# sensor-board.net
KiCad netlist of a schematic drawn in EAGLE
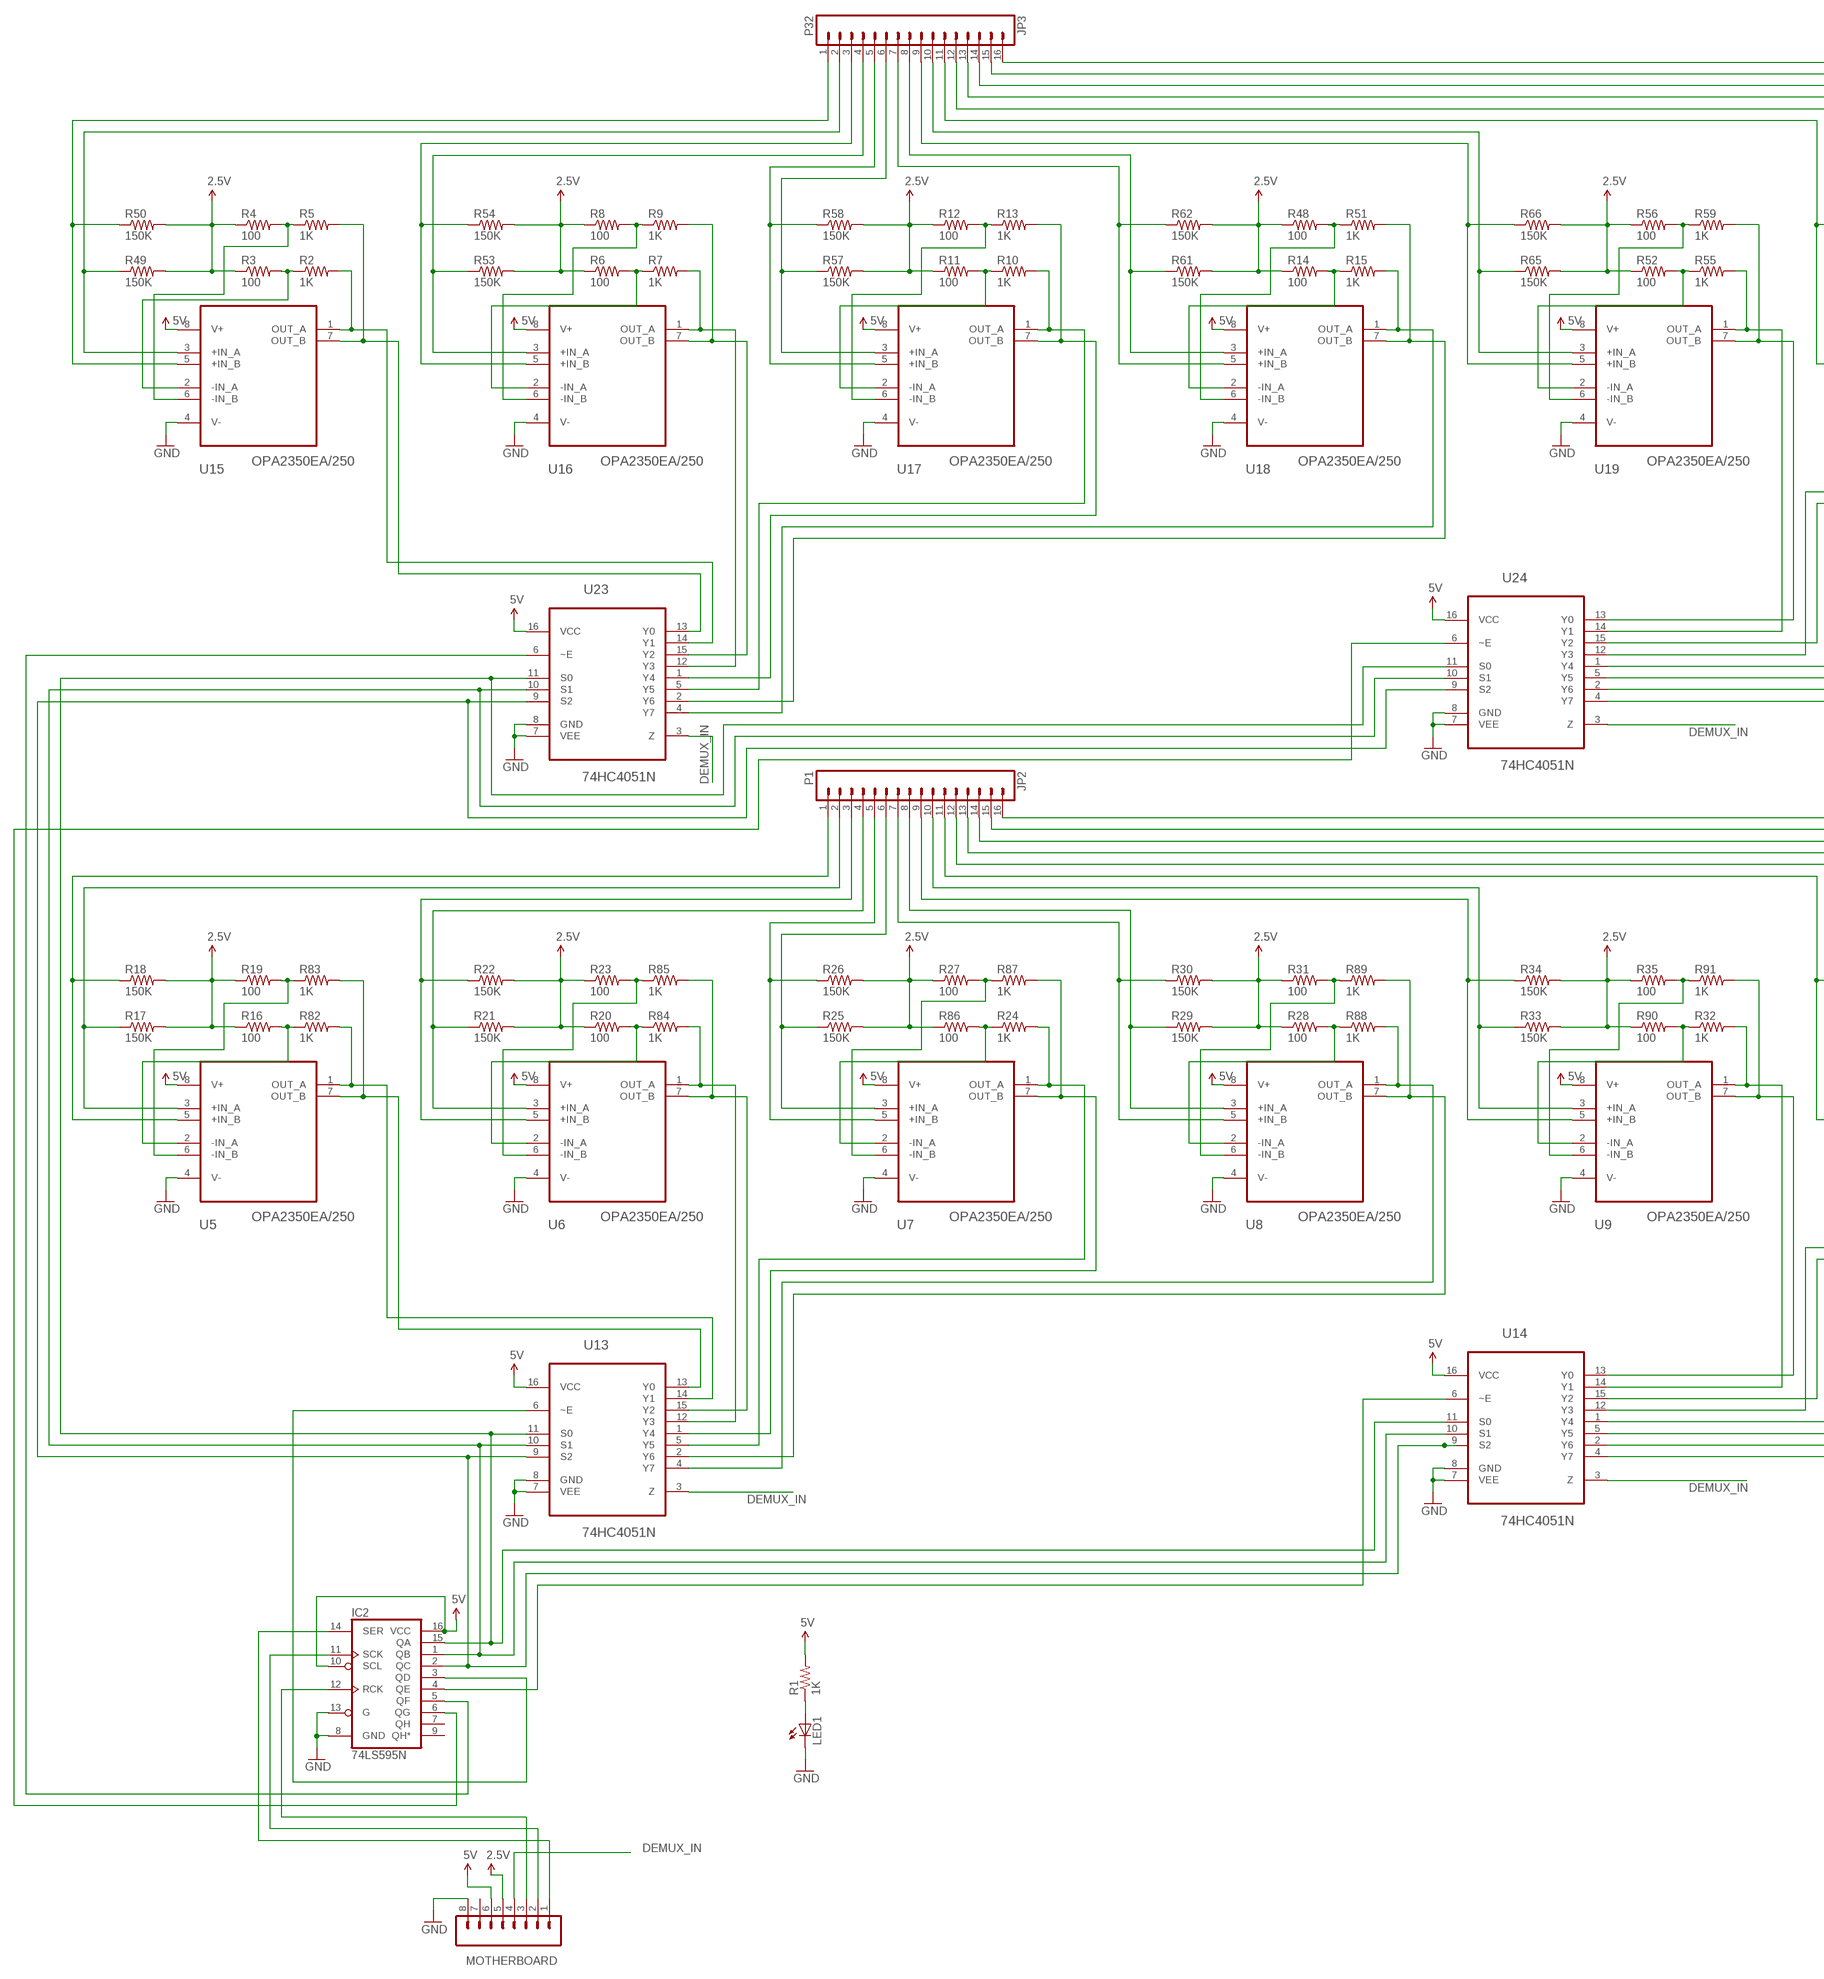
[diagram p0: schematic, sheet 1, part 1 of 2]
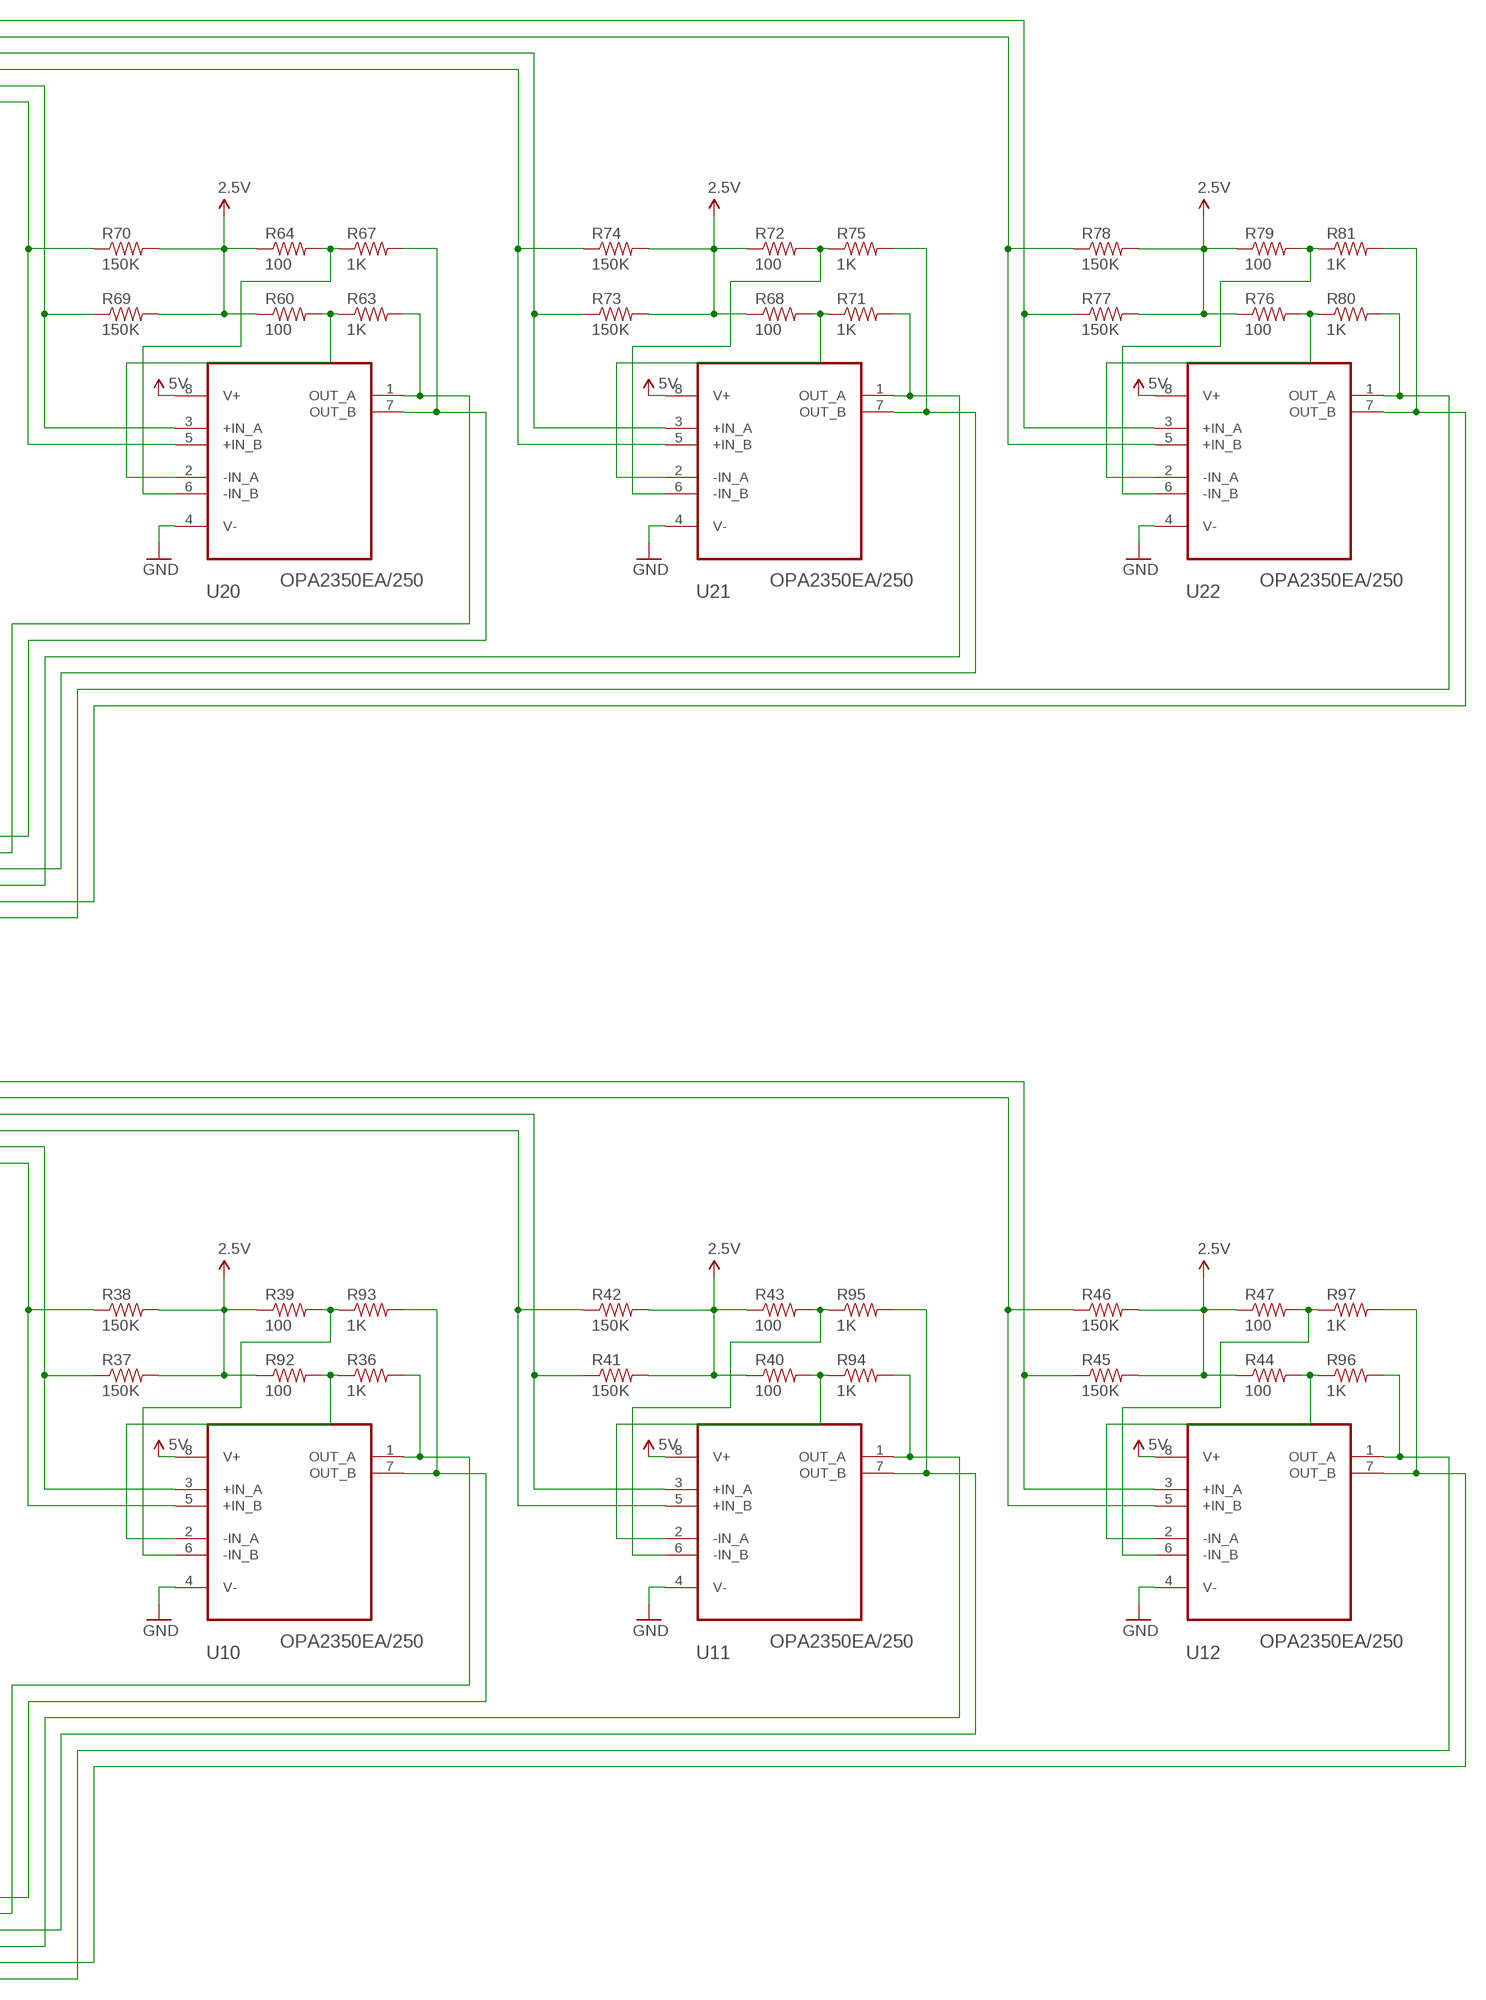
[diagram p1: schematic, sheet 1, part 2 of 2]

(export (version "E")
  (design (tool "Eeschema 10.0.6"))
  (components
    (comp (ref "IC2")
      (value "74LS595N")
      (footprint "eagle-import:DIL16")
      (libsource (lib "eagle-import") (part "74595NLS"))
    )
    (comp (ref "JP2")
      (value "P1")
      (footprint "eagle-import:1X16_LOCK")
      (libsource (lib "eagle-import") (part "M16LOCK"))
    )
    (comp (ref "JP3")
      (value "P32")
      (footprint "eagle-import:1X16_LOCK")
      (libsource (lib "eagle-import") (part "M16LOCK"))
    )
    (comp (ref "LED1")
      (value "LED0603")
      (footprint "eagle-import:LED-0603")
      (libsource (lib "eagle-import") (part "LED0603"))
    )
    (comp (ref "MOTHERBOARD")
      (value "M08LONGPADS")
      (footprint "eagle-import:1X08_LONGPADS")
      (libsource (lib "eagle-import") (part "M08LONGPADS"))
    )
    (comp (ref "R1")
      (value "1K")
      (footprint "eagle-import:0805")
      (libsource (lib "eagle-import") (part "RESISTOR0805-RES"))
    )
    (comp (ref "R2")
      (value "1K")
      (footprint "eagle-import:0805")
      (libsource (lib "eagle-import") (part "RESISTOR0805-RES"))
    )
    (comp (ref "R3")
      (value "100")
      (footprint "eagle-import:0805")
      (libsource (lib "eagle-import") (part "RESISTOR0805-RES"))
    )
    (comp (ref "R4")
      (value "100")
      (footprint "eagle-import:0805")
      (libsource (lib "eagle-import") (part "RESISTOR0805-RES"))
    )
    (comp (ref "R5")
      (value "1K")
      (footprint "eagle-import:0805")
      (libsource (lib "eagle-import") (part "RESISTOR0805-RES"))
    )
    (comp (ref "R6")
      (value "100")
      (footprint "eagle-import:0805")
      (libsource (lib "eagle-import") (part "RESISTOR0805-RES"))
    )
    (comp (ref "R7")
      (value "1K")
      (footprint "eagle-import:0805")
      (libsource (lib "eagle-import") (part "RESISTOR0805-RES"))
    )
    (comp (ref "R8")
      (value "100")
      (footprint "eagle-import:0805")
      (libsource (lib "eagle-import") (part "RESISTOR0805-RES"))
    )
    (comp (ref "R9")
      (value "1K")
      (footprint "eagle-import:0805")
      (libsource (lib "eagle-import") (part "RESISTOR0805-RES"))
    )
    (comp (ref "R10")
      (value "1K")
      (footprint "eagle-import:0805")
      (libsource (lib "eagle-import") (part "RESISTOR0805-RES"))
    )
    (comp (ref "R11")
      (value "100")
      (footprint "eagle-import:0805")
      (libsource (lib "eagle-import") (part "RESISTOR0805-RES"))
    )
    (comp (ref "R12")
      (value "100")
      (footprint "eagle-import:0805")
      (libsource (lib "eagle-import") (part "RESISTOR0805-RES"))
    )
    (comp (ref "R13")
      (value "1K")
      (footprint "eagle-import:0805")
      (libsource (lib "eagle-import") (part "RESISTOR0805-RES"))
    )
    (comp (ref "R14")
      (value "100")
      (footprint "eagle-import:0805")
      (libsource (lib "eagle-import") (part "RESISTOR0805-RES"))
    )
    (comp (ref "R15")
      (value "1K")
      (footprint "eagle-import:0805")
      (libsource (lib "eagle-import") (part "RESISTOR0805-RES"))
    )
    (comp (ref "R16")
      (value "100")
      (footprint "eagle-import:0805")
      (libsource (lib "eagle-import") (part "RESISTOR0805-RES"))
    )
    (comp (ref "R17")
      (value "150K")
      (footprint "eagle-import:0805")
      (libsource (lib "eagle-import") (part "RESISTOR0805-RES"))
    )
    (comp (ref "R18")
      (value "150K")
      (footprint "eagle-import:0805")
      (libsource (lib "eagle-import") (part "RESISTOR0805-RES"))
    )
    (comp (ref "R19")
      (value "100")
      (footprint "eagle-import:0805")
      (libsource (lib "eagle-import") (part "RESISTOR0805-RES"))
    )
    (comp (ref "R20")
      (value "100")
      (footprint "eagle-import:0805")
      (libsource (lib "eagle-import") (part "RESISTOR0805-RES"))
    )
    (comp (ref "R21")
      (value "150K")
      (footprint "eagle-import:0805")
      (libsource (lib "eagle-import") (part "RESISTOR0805-RES"))
    )
    (comp (ref "R22")
      (value "150K")
      (footprint "eagle-import:0805")
      (libsource (lib "eagle-import") (part "RESISTOR0805-RES"))
    )
    (comp (ref "R23")
      (value "100")
      (footprint "eagle-import:0805")
      (libsource (lib "eagle-import") (part "RESISTOR0805-RES"))
    )
    (comp (ref "R24")
      (value "1K")
      (footprint "eagle-import:0805")
      (libsource (lib "eagle-import") (part "RESISTOR0805-RES"))
    )
    (comp (ref "R25")
      (value "150K")
      (footprint "eagle-import:0805")
      (libsource (lib "eagle-import") (part "RESISTOR0805-RES"))
    )
    (comp (ref "R26")
      (value "150K")
      (footprint "eagle-import:0805")
      (libsource (lib "eagle-import") (part "RESISTOR0805-RES"))
    )
    (comp (ref "R27")
      (value "100")
      (footprint "eagle-import:0805")
      (libsource (lib "eagle-import") (part "RESISTOR0805-RES"))
    )
    (comp (ref "R28")
      (value "100")
      (footprint "eagle-import:0805")
      (libsource (lib "eagle-import") (part "RESISTOR0805-RES"))
    )
    (comp (ref "R29")
      (value "150K")
      (footprint "eagle-import:0805")
      (libsource (lib "eagle-import") (part "RESISTOR0805-RES"))
    )
    (comp (ref "R30")
      (value "150K")
      (footprint "eagle-import:0805")
      (libsource (lib "eagle-import") (part "RESISTOR0805-RES"))
    )
    (comp (ref "R31")
      (value "100")
      (footprint "eagle-import:0805")
      (libsource (lib "eagle-import") (part "RESISTOR0805-RES"))
    )
    (comp (ref "R32")
      (value "1K")
      (footprint "eagle-import:0805")
      (libsource (lib "eagle-import") (part "RESISTOR0805-RES"))
    )
    (comp (ref "R33")
      (value "150K")
      (footprint "eagle-import:0805")
      (libsource (lib "eagle-import") (part "RESISTOR0805-RES"))
    )
    (comp (ref "R34")
      (value "150K")
      (footprint "eagle-import:0805")
      (libsource (lib "eagle-import") (part "RESISTOR0805-RES"))
    )
    (comp (ref "R35")
      (value "100")
      (footprint "eagle-import:0805")
      (libsource (lib "eagle-import") (part "RESISTOR0805-RES"))
    )
    (comp (ref "R36")
      (value "1K")
      (footprint "eagle-import:0805")
      (libsource (lib "eagle-import") (part "RESISTOR0805-RES"))
    )
    (comp (ref "R37")
      (value "150K")
      (footprint "eagle-import:0805")
      (libsource (lib "eagle-import") (part "RESISTOR0805-RES"))
    )
    (comp (ref "R38")
      (value "150K")
      (footprint "eagle-import:0805")
      (libsource (lib "eagle-import") (part "RESISTOR0805-RES"))
    )
    (comp (ref "R39")
      (value "100")
      (footprint "eagle-import:0805")
      (libsource (lib "eagle-import") (part "RESISTOR0805-RES"))
    )
    (comp (ref "R40")
      (value "100")
      (footprint "eagle-import:0805")
      (libsource (lib "eagle-import") (part "RESISTOR0805-RES"))
    )
    (comp (ref "R41")
      (value "150K")
      (footprint "eagle-import:0805")
      (libsource (lib "eagle-import") (part "RESISTOR0805-RES"))
    )
    (comp (ref "R42")
      (value "150K")
      (footprint "eagle-import:0805")
      (libsource (lib "eagle-import") (part "RESISTOR0805-RES"))
    )
    (comp (ref "R43")
      (value "100")
      (footprint "eagle-import:0805")
      (libsource (lib "eagle-import") (part "RESISTOR0805-RES"))
    )
    (comp (ref "R44")
      (value "100")
      (footprint "eagle-import:0805")
      (libsource (lib "eagle-import") (part "RESISTOR0805-RES"))
    )
    (comp (ref "R45")
      (value "150K")
      (footprint "eagle-import:0805")
      (libsource (lib "eagle-import") (part "RESISTOR0805-RES"))
    )
    (comp (ref "R46")
      (value "150K")
      (footprint "eagle-import:0805")
      (libsource (lib "eagle-import") (part "RESISTOR0805-RES"))
    )
    (comp (ref "R47")
      (value "100")
      (footprint "eagle-import:0805")
      (libsource (lib "eagle-import") (part "RESISTOR0805-RES"))
    )
    (comp (ref "R48")
      (value "100")
      (footprint "eagle-import:0805")
      (libsource (lib "eagle-import") (part "RESISTOR0805-RES"))
    )
    (comp (ref "R49")
      (value "150K")
      (footprint "eagle-import:0805")
      (libsource (lib "eagle-import") (part "RESISTOR0805-RES"))
    )
    (comp (ref "R50")
      (value "150K")
      (footprint "eagle-import:0805")
      (libsource (lib "eagle-import") (part "RESISTOR0805-RES"))
    )
    (comp (ref "R51")
      (value "1K")
      (footprint "eagle-import:0805")
      (libsource (lib "eagle-import") (part "RESISTOR0805-RES"))
    )
    (comp (ref "R52")
      (value "100")
      (footprint "eagle-import:0805")
      (libsource (lib "eagle-import") (part "RESISTOR0805-RES"))
    )
    (comp (ref "R53")
      (value "150K")
      (footprint "eagle-import:0805")
      (libsource (lib "eagle-import") (part "RESISTOR0805-RES"))
    )
    (comp (ref "R54")
      (value "150K")
      (footprint "eagle-import:0805")
      (libsource (lib "eagle-import") (part "RESISTOR0805-RES"))
    )
    (comp (ref "R55")
      (value "1K")
      (footprint "eagle-import:0805")
      (libsource (lib "eagle-import") (part "RESISTOR0805-RES"))
    )
    (comp (ref "R56")
      (value "100")
      (footprint "eagle-import:0805")
      (libsource (lib "eagle-import") (part "RESISTOR0805-RES"))
    )
    (comp (ref "R57")
      (value "150K")
      (footprint "eagle-import:0805")
      (libsource (lib "eagle-import") (part "RESISTOR0805-RES"))
    )
    (comp (ref "R58")
      (value "150K")
      (footprint "eagle-import:0805")
      (libsource (lib "eagle-import") (part "RESISTOR0805-RES"))
    )
    (comp (ref "R59")
      (value "1K")
      (footprint "eagle-import:0805")
      (libsource (lib "eagle-import") (part "RESISTOR0805-RES"))
    )
    (comp (ref "R60")
      (value "100")
      (footprint "eagle-import:0805")
      (libsource (lib "eagle-import") (part "RESISTOR0805-RES"))
    )
    (comp (ref "R61")
      (value "150K")
      (footprint "eagle-import:0805")
      (libsource (lib "eagle-import") (part "RESISTOR0805-RES"))
    )
    (comp (ref "R62")
      (value "150K")
      (footprint "eagle-import:0805")
      (libsource (lib "eagle-import") (part "RESISTOR0805-RES"))
    )
    (comp (ref "R63")
      (value "1K")
      (footprint "eagle-import:0805")
      (libsource (lib "eagle-import") (part "RESISTOR0805-RES"))
    )
    (comp (ref "R64")
      (value "100")
      (footprint "eagle-import:0805")
      (libsource (lib "eagle-import") (part "RESISTOR0805-RES"))
    )
    (comp (ref "R65")
      (value "150K")
      (footprint "eagle-import:0805")
      (libsource (lib "eagle-import") (part "RESISTOR0805-RES"))
    )
    (comp (ref "R66")
      (value "150K")
      (footprint "eagle-import:0805")
      (libsource (lib "eagle-import") (part "RESISTOR0805-RES"))
    )
    (comp (ref "R67")
      (value "1K")
      (footprint "eagle-import:0805")
      (libsource (lib "eagle-import") (part "RESISTOR0805-RES"))
    )
    (comp (ref "R68")
      (value "100")
      (footprint "eagle-import:0805")
      (libsource (lib "eagle-import") (part "RESISTOR0805-RES"))
    )
    (comp (ref "R69")
      (value "150K")
      (footprint "eagle-import:0805")
      (libsource (lib "eagle-import") (part "RESISTOR0805-RES"))
    )
    (comp (ref "R70")
      (value "150K")
      (footprint "eagle-import:0805")
      (libsource (lib "eagle-import") (part "RESISTOR0805-RES"))
    )
    (comp (ref "R71")
      (value "1K")
      (footprint "eagle-import:0805")
      (libsource (lib "eagle-import") (part "RESISTOR0805-RES"))
    )
    (comp (ref "R72")
      (value "100")
      (footprint "eagle-import:0805")
      (libsource (lib "eagle-import") (part "RESISTOR0805-RES"))
    )
    (comp (ref "R73")
      (value "150K")
      (footprint "eagle-import:0805")
      (libsource (lib "eagle-import") (part "RESISTOR0805-RES"))
    )
    (comp (ref "R74")
      (value "150K")
      (footprint "eagle-import:0805")
      (libsource (lib "eagle-import") (part "RESISTOR0805-RES"))
    )
    (comp (ref "R75")
      (value "1K")
      (footprint "eagle-import:0805")
      (libsource (lib "eagle-import") (part "RESISTOR0805-RES"))
    )
    (comp (ref "R76")
      (value "100")
      (footprint "eagle-import:0805")
      (libsource (lib "eagle-import") (part "RESISTOR0805-RES"))
    )
    (comp (ref "R77")
      (value "150K")
      (footprint "eagle-import:0805")
      (libsource (lib "eagle-import") (part "RESISTOR0805-RES"))
    )
    (comp (ref "R78")
      (value "150K")
      (footprint "eagle-import:0805")
      (libsource (lib "eagle-import") (part "RESISTOR0805-RES"))
    )
    (comp (ref "R79")
      (value "100")
      (footprint "eagle-import:0805")
      (libsource (lib "eagle-import") (part "RESISTOR0805-RES"))
    )
    (comp (ref "R80")
      (value "1K")
      (footprint "eagle-import:0805")
      (libsource (lib "eagle-import") (part "RESISTOR0805-RES"))
    )
    (comp (ref "R81")
      (value "1K")
      (footprint "eagle-import:0805")
      (libsource (lib "eagle-import") (part "RESISTOR0805-RES"))
    )
    (comp (ref "R82")
      (value "1K")
      (footprint "eagle-import:0805")
      (libsource (lib "eagle-import") (part "RESISTOR0805-RES"))
    )
    (comp (ref "R83")
      (value "1K")
      (footprint "eagle-import:0805")
      (libsource (lib "eagle-import") (part "RESISTOR0805-RES"))
    )
    (comp (ref "R84")
      (value "1K")
      (footprint "eagle-import:0805")
      (libsource (lib "eagle-import") (part "RESISTOR0805-RES"))
    )
    (comp (ref "R85")
      (value "1K")
      (footprint "eagle-import:0805")
      (libsource (lib "eagle-import") (part "RESISTOR0805-RES"))
    )
    (comp (ref "R86")
      (value "100")
      (footprint "eagle-import:0805")
      (libsource (lib "eagle-import") (part "RESISTOR0805-RES"))
    )
    (comp (ref "R87")
      (value "1K")
      (footprint "eagle-import:0805")
      (libsource (lib "eagle-import") (part "RESISTOR0805-RES"))
    )
    (comp (ref "R88")
      (value "1K")
      (footprint "eagle-import:0805")
      (libsource (lib "eagle-import") (part "RESISTOR0805-RES"))
    )
    (comp (ref "R89")
      (value "1K")
      (footprint "eagle-import:0805")
      (libsource (lib "eagle-import") (part "RESISTOR0805-RES"))
    )
    (comp (ref "R90")
      (value "100")
      (footprint "eagle-import:0805")
      (libsource (lib "eagle-import") (part "RESISTOR0805-RES"))
    )
    (comp (ref "R91")
      (value "1K")
      (footprint "eagle-import:0805")
      (libsource (lib "eagle-import") (part "RESISTOR0805-RES"))
    )
    (comp (ref "R92")
      (value "100")
      (footprint "eagle-import:0805")
      (libsource (lib "eagle-import") (part "RESISTOR0805-RES"))
    )
    (comp (ref "R93")
      (value "1K")
      (footprint "eagle-import:0805")
      (libsource (lib "eagle-import") (part "RESISTOR0805-RES"))
    )
    (comp (ref "R94")
      (value "1K")
      (footprint "eagle-import:0805")
      (libsource (lib "eagle-import") (part "RESISTOR0805-RES"))
    )
    (comp (ref "R95")
      (value "1K")
      (footprint "eagle-import:0805")
      (libsource (lib "eagle-import") (part "RESISTOR0805-RES"))
    )
    (comp (ref "R96")
      (value "1K")
      (footprint "eagle-import:0805")
      (libsource (lib "eagle-import") (part "RESISTOR0805-RES"))
    )
    (comp (ref "R97")
      (value "1K")
      (footprint "eagle-import:0805")
      (libsource (lib "eagle-import") (part "RESISTOR0805-RES"))
    )
    (comp (ref "U5")
      (value "OPA2350EA/250")
      (footprint "eagle-import:SOP65P490X110-8N")
      (libsource (lib "eagle-import") (part "OPA2350EA/250"))
    )
    (comp (ref "U6")
      (value "OPA2350EA/250")
      (footprint "eagle-import:SOP65P490X110-8N")
      (libsource (lib "eagle-import") (part "OPA2350EA/250"))
    )
    (comp (ref "U7")
      (value "OPA2350EA/250")
      (footprint "eagle-import:SOP65P490X110-8N")
      (libsource (lib "eagle-import") (part "OPA2350EA/250"))
    )
    (comp (ref "U8")
      (value "OPA2350EA/250")
      (footprint "eagle-import:SOP65P490X110-8N")
      (libsource (lib "eagle-import") (part "OPA2350EA/250"))
    )
    (comp (ref "U9")
      (value "OPA2350EA/250")
      (footprint "eagle-import:SOP65P490X110-8N")
      (libsource (lib "eagle-import") (part "OPA2350EA/250"))
    )
    (comp (ref "U10")
      (value "OPA2350EA/250")
      (footprint "eagle-import:SOP65P490X110-8N")
      (libsource (lib "eagle-import") (part "OPA2350EA/250"))
    )
    (comp (ref "U11")
      (value "OPA2350EA/250")
      (footprint "eagle-import:SOP65P490X110-8N")
      (libsource (lib "eagle-import") (part "OPA2350EA/250"))
    )
    (comp (ref "U12")
      (value "OPA2350EA/250")
      (footprint "eagle-import:SOP65P490X110-8N")
      (libsource (lib "eagle-import") (part "OPA2350EA/250"))
    )
    (comp (ref "U13")
      (value "74HC4051N")
      (footprint "eagle-import:DIP254P762X420-16")
      (libsource (lib "eagle-import") (part "74HC4051N"))
    )
    (comp (ref "U14")
      (value "74HC4051N")
      (footprint "eagle-import:DIP254P762X420-16")
      (libsource (lib "eagle-import") (part "74HC4051N"))
    )
    (comp (ref "U15")
      (value "OPA2350EA/250")
      (footprint "eagle-import:SOP65P490X110-8N")
      (libsource (lib "eagle-import") (part "OPA2350EA/250"))
    )
    (comp (ref "U16")
      (value "OPA2350EA/250")
      (footprint "eagle-import:SOP65P490X110-8N")
      (libsource (lib "eagle-import") (part "OPA2350EA/250"))
    )
    (comp (ref "U17")
      (value "OPA2350EA/250")
      (footprint "eagle-import:SOP65P490X110-8N")
      (libsource (lib "eagle-import") (part "OPA2350EA/250"))
    )
    (comp (ref "U18")
      (value "OPA2350EA/250")
      (footprint "eagle-import:SOP65P490X110-8N")
      (libsource (lib "eagle-import") (part "OPA2350EA/250"))
    )
    (comp (ref "U19")
      (value "OPA2350EA/250")
      (footprint "eagle-import:SOP65P490X110-8N")
      (libsource (lib "eagle-import") (part "OPA2350EA/250"))
    )
    (comp (ref "U20")
      (value "OPA2350EA/250")
      (footprint "eagle-import:SOP65P490X110-8N")
      (libsource (lib "eagle-import") (part "OPA2350EA/250"))
    )
    (comp (ref "U21")
      (value "OPA2350EA/250")
      (footprint "eagle-import:SOP65P490X110-8N")
      (libsource (lib "eagle-import") (part "OPA2350EA/250"))
    )
    (comp (ref "U22")
      (value "OPA2350EA/250")
      (footprint "eagle-import:SOP65P490X110-8N")
      (libsource (lib "eagle-import") (part "OPA2350EA/250"))
    )
    (comp (ref "U23")
      (value "74HC4051N")
      (footprint "eagle-import:DIP254P762X420-16")
      (libsource (lib "eagle-import") (part "74HC4051N"))
    )
    (comp (ref "U24")
      (value "74HC4051N")
      (footprint "eagle-import:DIP254P762X420-16")
      (libsource (lib "eagle-import") (part "74HC4051N"))
    )
  )
  (nets
    (net (code "1") (name "/DEMUX_IN") (class "Default")
      (node (ref "MOTHERBOARD") (pin "4") (pinfunction "4_4") (pintype "passive"))
      (node (ref "U13") (pin "3") (pinfunction "Z_3") (pintype "bidirectional"))
      (node (ref "U14") (pin "3") (pinfunction "Z_3") (pintype "bidirectional"))
      (node (ref "U23") (pin "3") (pinfunction "Z_3") (pintype "bidirectional"))
      (node (ref "U24") (pin "3") (pinfunction "Z_3") (pintype "bidirectional"))
    )
    (net (code "2") (name "2.5V") (class "Default")
      (node (ref "MOTHERBOARD") (pin "5") (pinfunction "5_5") (pintype "passive"))
      (node (ref "R11") (pin "1") (pinfunction "1_1") (pintype "passive"))
      (node (ref "R12") (pin "1") (pinfunction "1_1") (pintype "passive"))
      (node (ref "R14") (pin "1") (pinfunction "1_1") (pintype "passive"))
      (node (ref "R16") (pin "1") (pinfunction "1_1") (pintype "passive"))
      (node (ref "R17") (pin "2") (pinfunction "2_2") (pintype "passive"))
      (node (ref "R18") (pin "2") (pinfunction "2_2") (pintype "passive"))
      (node (ref "R19") (pin "1") (pinfunction "1_1") (pintype "passive"))
      (node (ref "R20") (pin "1") (pinfunction "1_1") (pintype "passive"))
      (node (ref "R21") (pin "2") (pinfunction "2_2") (pintype "passive"))
      (node (ref "R22") (pin "2") (pinfunction "2_2") (pintype "passive"))
      (node (ref "R23") (pin "1") (pinfunction "1_1") (pintype "passive"))
      (node (ref "R25") (pin "2") (pinfunction "2_2") (pintype "passive"))
      (node (ref "R26") (pin "2") (pinfunction "2_2") (pintype "passive"))
      (node (ref "R27") (pin "1") (pinfunction "1_1") (pintype "passive"))
      (node (ref "R28") (pin "1") (pinfunction "1_1") (pintype "passive"))
      (node (ref "R29") (pin "2") (pinfunction "2_2") (pintype "passive"))
      (node (ref "R3") (pin "1") (pinfunction "1_1") (pintype "passive"))
      (node (ref "R30") (pin "2") (pinfunction "2_2") (pintype "passive"))
      (node (ref "R31") (pin "1") (pinfunction "1_1") (pintype "passive"))
      (node (ref "R33") (pin "2") (pinfunction "2_2") (pintype "passive"))
      (node (ref "R34") (pin "2") (pinfunction "2_2") (pintype "passive"))
      (node (ref "R35") (pin "1") (pinfunction "1_1") (pintype "passive"))
      (node (ref "R37") (pin "2") (pinfunction "2_2") (pintype "passive"))
      (node (ref "R38") (pin "2") (pinfunction "2_2") (pintype "passive"))
      (node (ref "R39") (pin "1") (pinfunction "1_1") (pintype "passive"))
      (node (ref "R4") (pin "1") (pinfunction "1_1") (pintype "passive"))
      (node (ref "R40") (pin "1") (pinfunction "1_1") (pintype "passive"))
      (node (ref "R41") (pin "2") (pinfunction "2_2") (pintype "passive"))
      (node (ref "R42") (pin "2") (pinfunction "2_2") (pintype "passive"))
      (node (ref "R43") (pin "1") (pinfunction "1_1") (pintype "passive"))
      (node (ref "R44") (pin "1") (pinfunction "1_1") (pintype "passive"))
      (node (ref "R45") (pin "2") (pinfunction "2_2") (pintype "passive"))
      (node (ref "R46") (pin "2") (pinfunction "2_2") (pintype "passive"))
      (node (ref "R47") (pin "1") (pinfunction "1_1") (pintype "passive"))
      (node (ref "R48") (pin "1") (pinfunction "1_1") (pintype "passive"))
      (node (ref "R49") (pin "2") (pinfunction "2_2") (pintype "passive"))
      (node (ref "R50") (pin "2") (pinfunction "2_2") (pintype "passive"))
      (node (ref "R52") (pin "1") (pinfunction "1_1") (pintype "passive"))
      (node (ref "R53") (pin "2") (pinfunction "2_2") (pintype "passive"))
      (node (ref "R54") (pin "2") (pinfunction "2_2") (pintype "passive"))
      (node (ref "R56") (pin "1") (pinfunction "1_1") (pintype "passive"))
      (node (ref "R57") (pin "2") (pinfunction "2_2") (pintype "passive"))
      (node (ref "R58") (pin "2") (pinfunction "2_2") (pintype "passive"))
      (node (ref "R6") (pin "1") (pinfunction "1_1") (pintype "passive"))
      (node (ref "R60") (pin "1") (pinfunction "1_1") (pintype "passive"))
      (node (ref "R61") (pin "2") (pinfunction "2_2") (pintype "passive"))
      (node (ref "R62") (pin "2") (pinfunction "2_2") (pintype "passive"))
      (node (ref "R64") (pin "1") (pinfunction "1_1") (pintype "passive"))
      (node (ref "R65") (pin "2") (pinfunction "2_2") (pintype "passive"))
      (node (ref "R66") (pin "2") (pinfunction "2_2") (pintype "passive"))
      (node (ref "R68") (pin "1") (pinfunction "1_1") (pintype "passive"))
      (node (ref "R69") (pin "2") (pinfunction "2_2") (pintype "passive"))
      (node (ref "R70") (pin "2") (pinfunction "2_2") (pintype "passive"))
      (node (ref "R72") (pin "1") (pinfunction "1_1") (pintype "passive"))
      (node (ref "R73") (pin "2") (pinfunction "2_2") (pintype "passive"))
      (node (ref "R74") (pin "2") (pinfunction "2_2") (pintype "passive"))
      (node (ref "R76") (pin "1") (pinfunction "1_1") (pintype "passive"))
      (node (ref "R77") (pin "2") (pinfunction "2_2") (pintype "passive"))
      (node (ref "R78") (pin "2") (pinfunction "2_2") (pintype "passive"))
      (node (ref "R79") (pin "1") (pinfunction "1_1") (pintype "passive"))
      (node (ref "R8") (pin "1") (pinfunction "1_1") (pintype "passive"))
      (node (ref "R86") (pin "1") (pinfunction "1_1") (pintype "passive"))
      (node (ref "R90") (pin "1") (pinfunction "1_1") (pintype "passive"))
      (node (ref "R92") (pin "1") (pinfunction "1_1") (pintype "passive"))
    )
    (net (code "3") (name "5V") (class "Default")
      (node (ref "IC2") (pin "10") (pinfunction "SCL_10") (pintype "input"))
      (node (ref "IC2") (pin "16") (pinfunction "VCC_16") (pintype "power_in"))
      (node (ref "MOTHERBOARD") (pin "6") (pinfunction "6_6") (pintype "passive"))
      (node (ref "R1") (pin "2") (pinfunction "2_2") (pintype "passive"))
      (node (ref "U10") (pin "8") (pinfunction "V+_8") (pintype "power_in"))
      (node (ref "U11") (pin "8") (pinfunction "V+_8") (pintype "power_in"))
      (node (ref "U12") (pin "8") (pinfunction "V+_8") (pintype "power_in"))
      (node (ref "U13") (pin "16") (pinfunction "VCC_16") (pintype "power_in"))
      (node (ref "U14") (pin "16") (pinfunction "VCC_16") (pintype "power_in"))
      (node (ref "U15") (pin "8") (pinfunction "V+_8") (pintype "power_in"))
      (node (ref "U16") (pin "8") (pinfunction "V+_8") (pintype "power_in"))
      (node (ref "U17") (pin "8") (pinfunction "V+_8") (pintype "power_in"))
      (node (ref "U18") (pin "8") (pinfunction "V+_8") (pintype "power_in"))
      (node (ref "U19") (pin "8") (pinfunction "V+_8") (pintype "power_in"))
      (node (ref "U20") (pin "8") (pinfunction "V+_8") (pintype "power_in"))
      (node (ref "U21") (pin "8") (pinfunction "V+_8") (pintype "power_in"))
      (node (ref "U22") (pin "8") (pinfunction "V+_8") (pintype "power_in"))
      (node (ref "U23") (pin "16") (pinfunction "VCC_16") (pintype "power_in"))
      (node (ref "U24") (pin "16") (pinfunction "VCC_16") (pintype "power_in"))
      (node (ref "U5") (pin "8") (pinfunction "V+_8") (pintype "power_in"))
      (node (ref "U6") (pin "8") (pinfunction "V+_8") (pintype "power_in"))
      (node (ref "U7") (pin "8") (pinfunction "V+_8") (pintype "power_in"))
      (node (ref "U8") (pin "8") (pinfunction "V+_8") (pintype "power_in"))
      (node (ref "U9") (pin "8") (pinfunction "V+_8") (pintype "power_in"))
    )
    (net (code "4") (name "GND") (class "Default")
      (node (ref "IC2") (pin "13") (pinfunction "G_13") (pintype "input"))
      (node (ref "IC2") (pin "8") (pinfunction "GND_8") (pintype "power_in"))
      (node (ref "LED1") (pin "C") (pinfunction "C_C") (pintype "passive"))
      (node (ref "MOTHERBOARD") (pin "8") (pinfunction "8_8") (pintype "passive"))
      (node (ref "U10") (pin "4") (pinfunction "V-_4") (pintype "power_in"))
      (node (ref "U11") (pin "4") (pinfunction "V-_4") (pintype "power_in"))
      (node (ref "U12") (pin "4") (pinfunction "V-_4") (pintype "power_in"))
      (node (ref "U13") (pin "7") (pinfunction "VEE_7") (pintype "power_in"))
      (node (ref "U13") (pin "8") (pinfunction "GND_8") (pintype "passive"))
      (node (ref "U14") (pin "7") (pinfunction "VEE_7") (pintype "power_in"))
      (node (ref "U14") (pin "8") (pinfunction "GND_8") (pintype "passive"))
      (node (ref "U15") (pin "4") (pinfunction "V-_4") (pintype "power_in"))
      (node (ref "U16") (pin "4") (pinfunction "V-_4") (pintype "power_in"))
      (node (ref "U17") (pin "4") (pinfunction "V-_4") (pintype "power_in"))
      (node (ref "U18") (pin "4") (pinfunction "V-_4") (pintype "power_in"))
      (node (ref "U19") (pin "4") (pinfunction "V-_4") (pintype "power_in"))
      (node (ref "U20") (pin "4") (pinfunction "V-_4") (pintype "power_in"))
      (node (ref "U21") (pin "4") (pinfunction "V-_4") (pintype "power_in"))
      (node (ref "U22") (pin "4") (pinfunction "V-_4") (pintype "power_in"))
      (node (ref "U23") (pin "7") (pinfunction "VEE_7") (pintype "power_in"))
      (node (ref "U23") (pin "8") (pinfunction "GND_8") (pintype "passive"))
      (node (ref "U24") (pin "7") (pinfunction "VEE_7") (pintype "power_in"))
      (node (ref "U24") (pin "8") (pinfunction "GND_8") (pintype "passive"))
      (node (ref "U5") (pin "4") (pinfunction "V-_4") (pintype "power_in"))
      (node (ref "U6") (pin "4") (pinfunction "V-_4") (pintype "power_in"))
      (node (ref "U7") (pin "4") (pinfunction "V-_4") (pintype "power_in"))
      (node (ref "U8") (pin "4") (pinfunction "V-_4") (pintype "power_in"))
      (node (ref "U9") (pin "4") (pinfunction "V-_4") (pintype "power_in"))
    )
    (net (code "5") (name "Net-(IC2-QA)") (class "Default")
      (node (ref "IC2") (pin "15") (pinfunction "QA_15") (pintype "tri_state"))
      (node (ref "U13") (pin "11") (pinfunction "S0_11") (pintype "input"))
      (node (ref "U14") (pin "11") (pinfunction "S0_11") (pintype "input"))
      (node (ref "U23") (pin "11") (pinfunction "S0_11") (pintype "input"))
      (node (ref "U24") (pin "11") (pinfunction "S0_11") (pintype "input"))
    )
    (net (code "6") (name "Net-(IC2-QB)") (class "Default")
      (node (ref "IC2") (pin "1") (pinfunction "QB_1") (pintype "tri_state"))
      (node (ref "U13") (pin "10") (pinfunction "S1_10") (pintype "input"))
      (node (ref "U14") (pin "10") (pinfunction "S1_10") (pintype "input"))
      (node (ref "U23") (pin "10") (pinfunction "S1_10") (pintype "input"))
      (node (ref "U24") (pin "10") (pinfunction "S1_10") (pintype "input"))
    )
    (net (code "7") (name "Net-(IC2-QC)") (class "Default")
      (node (ref "IC2") (pin "2") (pinfunction "QC_2") (pintype "tri_state"))
      (node (ref "U13") (pin "9") (pinfunction "S2_9") (pintype "input"))
      (node (ref "U14") (pin "9") (pinfunction "S2_9") (pintype "input"))
      (node (ref "U23") (pin "9") (pinfunction "S2_9") (pintype "input"))
      (node (ref "U24") (pin "9") (pinfunction "S2_9") (pintype "input"))
    )
    (net (code "8") (name "Net-(IC2-QD)") (class "Default")
      (node (ref "IC2") (pin "3") (pinfunction "QD_3") (pintype "tri_state"))
      (node (ref "U13") (pin "6") (pinfunction "~{E}_6") (pintype "input"))
    )
    (net (code "9") (name "Net-(IC2-QE)") (class "Default")
      (node (ref "IC2") (pin "4") (pinfunction "QE_4") (pintype "tri_state"))
      (node (ref "U14") (pin "6") (pinfunction "~{E}_6") (pintype "input"))
    )
    (net (code "10") (name "Net-(IC2-QF)") (class "Default")
      (node (ref "IC2") (pin "5") (pinfunction "QF_5") (pintype "tri_state"))
      (node (ref "U23") (pin "6") (pinfunction "~{E}_6") (pintype "input"))
    )
    (net (code "11") (name "Net-(IC2-QG)") (class "Default")
      (node (ref "IC2") (pin "6") (pinfunction "QG_6") (pintype "tri_state"))
      (node (ref "U24") (pin "6") (pinfunction "~{E}_6") (pintype "input"))
    )
    (net (code "12") (name "Net-(IC2-RCK)") (class "Default")
      (node (ref "IC2") (pin "12") (pinfunction "RCK_12") (pintype "input"))
      (node (ref "MOTHERBOARD") (pin "3") (pinfunction "3_3") (pintype "passive"))
    )
    (net (code "13") (name "Net-(IC2-SCK)") (class "Default")
      (node (ref "IC2") (pin "11") (pinfunction "SCK_11") (pintype "input"))
      (node (ref "MOTHERBOARD") (pin "2") (pinfunction "2_2") (pintype "passive"))
    )
    (net (code "14") (name "Net-(IC2-SER)") (class "Default")
      (node (ref "IC2") (pin "14") (pinfunction "SER_14") (pintype "input"))
      (node (ref "MOTHERBOARD") (pin "1") (pinfunction "1_1") (pintype "passive"))
    )
    (net (code "15") (name "Net-(LED1-PadA)") (class "Default")
      (node (ref "LED1") (pin "A") (pinfunction "A_A") (pintype "passive"))
      (node (ref "R1") (pin "1") (pinfunction "1_1") (pintype "passive"))
    )
    (net (code "16") (name "Net-(U5-+IN_A)") (class "Default")
      (node (ref "JP2") (pin "2") (pinfunction "2_2") (pintype "passive"))
      (node (ref "R17") (pin "1") (pinfunction "1_1") (pintype "passive"))
      (node (ref "U5") (pin "3") (pinfunction "+IN_A_3") (pintype "input"))
    )
    (net (code "17") (name "Net-(U5-+IN_B)") (class "Default")
      (node (ref "JP2") (pin "1") (pinfunction "1_1") (pintype "passive"))
      (node (ref "R18") (pin "1") (pinfunction "1_1") (pintype "passive"))
      (node (ref "U5") (pin "5") (pinfunction "+IN_B_5") (pintype "input"))
    )
    (net (code "18") (name "Net-(U5--IN_A)") (class "Default")
      (node (ref "R16") (pin "2") (pinfunction "2_2") (pintype "passive"))
      (node (ref "R82") (pin "1") (pinfunction "1_1") (pintype "passive"))
      (node (ref "U5") (pin "2") (pinfunction "-IN_A_2") (pintype "input"))
    )
    (net (code "19") (name "Net-(U5--IN_B)") (class "Default")
      (node (ref "R19") (pin "2") (pinfunction "2_2") (pintype "passive"))
      (node (ref "R83") (pin "1") (pinfunction "1_1") (pintype "passive"))
      (node (ref "U5") (pin "6") (pinfunction "-IN_B_6") (pintype "input"))
    )
    (net (code "20") (name "Net-(U6-+IN_A)") (class "Default")
      (node (ref "JP2") (pin "4") (pinfunction "4_4") (pintype "passive"))
      (node (ref "R21") (pin "1") (pinfunction "1_1") (pintype "passive"))
      (node (ref "U6") (pin "3") (pinfunction "+IN_A_3") (pintype "input"))
    )
    (net (code "21") (name "Net-(U6-+IN_B)") (class "Default")
      (node (ref "JP2") (pin "3") (pinfunction "3_3") (pintype "passive"))
      (node (ref "R22") (pin "1") (pinfunction "1_1") (pintype "passive"))
      (node (ref "U6") (pin "5") (pinfunction "+IN_B_5") (pintype "input"))
    )
    (net (code "22") (name "Net-(U6--IN_A)") (class "Default")
      (node (ref "R20") (pin "2") (pinfunction "2_2") (pintype "passive"))
      (node (ref "R84") (pin "1") (pinfunction "1_1") (pintype "passive"))
      (node (ref "U6") (pin "2") (pinfunction "-IN_A_2") (pintype "input"))
    )
    (net (code "23") (name "Net-(U6--IN_B)") (class "Default")
      (node (ref "R23") (pin "2") (pinfunction "2_2") (pintype "passive"))
      (node (ref "R85") (pin "1") (pinfunction "1_1") (pintype "passive"))
      (node (ref "U6") (pin "6") (pinfunction "-IN_B_6") (pintype "input"))
    )
    (net (code "24") (name "Net-(U7-+IN_A)") (class "Default")
      (node (ref "JP2") (pin "6") (pinfunction "6_6") (pintype "passive"))
      (node (ref "R25") (pin "1") (pinfunction "1_1") (pintype "passive"))
      (node (ref "U7") (pin "3") (pinfunction "+IN_A_3") (pintype "input"))
    )
    (net (code "25") (name "Net-(U7-+IN_B)") (class "Default")
      (node (ref "JP2") (pin "5") (pinfunction "5_5") (pintype "passive"))
      (node (ref "R26") (pin "1") (pinfunction "1_1") (pintype "passive"))
      (node (ref "U7") (pin "5") (pinfunction "+IN_B_5") (pintype "input"))
    )
    (net (code "26") (name "Net-(U7--IN_A)") (class "Default")
      (node (ref "R24") (pin "1") (pinfunction "1_1") (pintype "passive"))
      (node (ref "R86") (pin "2") (pinfunction "2_2") (pintype "passive"))
      (node (ref "U7") (pin "2") (pinfunction "-IN_A_2") (pintype "input"))
    )
    (net (code "27") (name "Net-(U7--IN_B)") (class "Default")
      (node (ref "R27") (pin "2") (pinfunction "2_2") (pintype "passive"))
      (node (ref "R87") (pin "1") (pinfunction "1_1") (pintype "passive"))
      (node (ref "U7") (pin "6") (pinfunction "-IN_B_6") (pintype "input"))
    )
    (net (code "28") (name "Net-(U8-+IN_A)") (class "Default")
      (node (ref "JP2") (pin "8") (pinfunction "8_8") (pintype "passive"))
      (node (ref "R29") (pin "1") (pinfunction "1_1") (pintype "passive"))
      (node (ref "U8") (pin "3") (pinfunction "+IN_A_3") (pintype "input"))
    )
    (net (code "29") (name "Net-(U8-+IN_B)") (class "Default")
      (node (ref "JP2") (pin "7") (pinfunction "7_7") (pintype "passive"))
      (node (ref "R30") (pin "1") (pinfunction "1_1") (pintype "passive"))
      (node (ref "U8") (pin "5") (pinfunction "+IN_B_5") (pintype "input"))
    )
    (net (code "30") (name "Net-(U8--IN_A)") (class "Default")
      (node (ref "R28") (pin "2") (pinfunction "2_2") (pintype "passive"))
      (node (ref "R88") (pin "1") (pinfunction "1_1") (pintype "passive"))
      (node (ref "U8") (pin "2") (pinfunction "-IN_A_2") (pintype "input"))
    )
    (net (code "31") (name "Net-(U8--IN_B)") (class "Default")
      (node (ref "R31") (pin "2") (pinfunction "2_2") (pintype "passive"))
      (node (ref "R89") (pin "1") (pinfunction "1_1") (pintype "passive"))
      (node (ref "U8") (pin "6") (pinfunction "-IN_B_6") (pintype "input"))
    )
    (net (code "32") (name "Net-(U9-+IN_A)") (class "Default")
      (node (ref "JP2") (pin "10") (pinfunction "10_10") (pintype "passive"))
      (node (ref "R33") (pin "1") (pinfunction "1_1") (pintype "passive"))
      (node (ref "U9") (pin "3") (pinfunction "+IN_A_3") (pintype "input"))
    )
    (net (code "33") (name "Net-(U9-+IN_B)") (class "Default")
      (node (ref "JP2") (pin "9") (pinfunction "9_9") (pintype "passive"))
      (node (ref "R34") (pin "1") (pinfunction "1_1") (pintype "passive"))
      (node (ref "U9") (pin "5") (pinfunction "+IN_B_5") (pintype "input"))
    )
    (net (code "34") (name "Net-(U9--IN_A)") (class "Default")
      (node (ref "R32") (pin "1") (pinfunction "1_1") (pintype "passive"))
      (node (ref "R90") (pin "2") (pinfunction "2_2") (pintype "passive"))
      (node (ref "U9") (pin "2") (pinfunction "-IN_A_2") (pintype "input"))
    )
    (net (code "35") (name "Net-(U9--IN_B)") (class "Default")
      (node (ref "R35") (pin "2") (pinfunction "2_2") (pintype "passive"))
      (node (ref "R91") (pin "1") (pinfunction "1_1") (pintype "passive"))
      (node (ref "U9") (pin "6") (pinfunction "-IN_B_6") (pintype "input"))
    )
    (net (code "36") (name "Net-(U10-+IN_A)") (class "Default")
      (node (ref "JP2") (pin "12") (pinfunction "12_12") (pintype "passive"))
      (node (ref "R37") (pin "1") (pinfunction "1_1") (pintype "passive"))
      (node (ref "U10") (pin "3") (pinfunction "+IN_A_3") (pintype "input"))
    )
    (net (code "37") (name "Net-(U10-+IN_B)") (class "Default")
      (node (ref "JP2") (pin "11") (pinfunction "11_11") (pintype "passive"))
      (node (ref "R38") (pin "1") (pinfunction "1_1") (pintype "passive"))
      (node (ref "U10") (pin "5") (pinfunction "+IN_B_5") (pintype "input"))
    )
    (net (code "38") (name "Net-(U10--IN_A)") (class "Default")
      (node (ref "R36") (pin "1") (pinfunction "1_1") (pintype "passive"))
      (node (ref "R92") (pin "2") (pinfunction "2_2") (pintype "passive"))
      (node (ref "U10") (pin "2") (pinfunction "-IN_A_2") (pintype "input"))
    )
    (net (code "39") (name "Net-(U10--IN_B)") (class "Default")
      (node (ref "R39") (pin "2") (pinfunction "2_2") (pintype "passive"))
      (node (ref "R93") (pin "1") (pinfunction "1_1") (pintype "passive"))
      (node (ref "U10") (pin "6") (pinfunction "-IN_B_6") (pintype "input"))
    )
    (net (code "40") (name "Net-(U10-OUT_A)") (class "Default")
      (node (ref "R36") (pin "2") (pinfunction "2_2") (pintype "passive"))
      (node (ref "U10") (pin "1") (pinfunction "OUT_A_1") (pintype "output"))
      (node (ref "U14") (pin "12") (pinfunction "Y3_12") (pintype "bidirectional"))
    )
    (net (code "41") (name "Net-(U10-OUT_B)") (class "Default")
      (node (ref "R93") (pin "2") (pinfunction "2_2") (pintype "passive"))
      (node (ref "U10") (pin "7") (pinfunction "OUT_B_7") (pintype "output"))
      (node (ref "U14") (pin "15") (pinfunction "Y2_15") (pintype "bidirectional"))
    )
    (net (code "42") (name "Net-(U11-+IN_A)") (class "Default")
      (node (ref "JP2") (pin "14") (pinfunction "14_14") (pintype "passive"))
      (node (ref "R41") (pin "1") (pinfunction "1_1") (pintype "passive"))
      (node (ref "U11") (pin "3") (pinfunction "+IN_A_3") (pintype "input"))
    )
    (net (code "43") (name "Net-(U11-+IN_B)") (class "Default")
      (node (ref "JP2") (pin "13") (pinfunction "13_13") (pintype "passive"))
      (node (ref "R42") (pin "1") (pinfunction "1_1") (pintype "passive"))
      (node (ref "U11") (pin "5") (pinfunction "+IN_B_5") (pintype "input"))
    )
    (net (code "44") (name "Net-(U11--IN_A)") (class "Default")
      (node (ref "R40") (pin "2") (pinfunction "2_2") (pintype "passive"))
      (node (ref "R94") (pin "1") (pinfunction "1_1") (pintype "passive"))
      (node (ref "U11") (pin "2") (pinfunction "-IN_A_2") (pintype "input"))
    )
    (net (code "45") (name "Net-(U11--IN_B)") (class "Default")
      (node (ref "R43") (pin "2") (pinfunction "2_2") (pintype "passive"))
      (node (ref "R95") (pin "1") (pinfunction "1_1") (pintype "passive"))
      (node (ref "U11") (pin "6") (pinfunction "-IN_B_6") (pintype "input"))
    )
    (net (code "46") (name "Net-(U11-OUT_A)") (class "Default")
      (node (ref "R94") (pin "2") (pinfunction "2_2") (pintype "passive"))
      (node (ref "U11") (pin "1") (pinfunction "OUT_A_1") (pintype "output"))
      (node (ref "U14") (pin "5") (pinfunction "Y5_5") (pintype "bidirectional"))
    )
    (net (code "47") (name "Net-(U11-OUT_B)") (class "Default")
      (node (ref "R95") (pin "2") (pinfunction "2_2") (pintype "passive"))
      (node (ref "U11") (pin "7") (pinfunction "OUT_B_7") (pintype "output"))
      (node (ref "U14") (pin "1") (pinfunction "Y4_1") (pintype "bidirectional"))
    )
    (net (code "48") (name "Net-(U12-+IN_A)") (class "Default")
      (node (ref "JP2") (pin "16") (pinfunction "16_16") (pintype "passive"))
      (node (ref "R45") (pin "1") (pinfunction "1_1") (pintype "passive"))
      (node (ref "U12") (pin "3") (pinfunction "+IN_A_3") (pintype "input"))
    )
    (net (code "49") (name "Net-(U12-+IN_B)") (class "Default")
      (node (ref "JP2") (pin "15") (pinfunction "15_15") (pintype "passive"))
      (node (ref "R46") (pin "1") (pinfunction "1_1") (pintype "passive"))
      (node (ref "U12") (pin "5") (pinfunction "+IN_B_5") (pintype "input"))
    )
    (net (code "50") (name "Net-(U12--IN_A)") (class "Default")
      (node (ref "R44") (pin "2") (pinfunction "2_2") (pintype "passive"))
      (node (ref "R96") (pin "1") (pinfunction "1_1") (pintype "passive"))
      (node (ref "U12") (pin "2") (pinfunction "-IN_A_2") (pintype "input"))
    )
    (net (code "51") (name "Net-(U12--IN_B)") (class "Default")
      (node (ref "R47") (pin "2") (pinfunction "2_2") (pintype "passive"))
      (node (ref "R97") (pin "1") (pinfunction "1_1") (pintype "passive"))
      (node (ref "U12") (pin "6") (pinfunction "-IN_B_6") (pintype "input"))
    )
    (net (code "52") (name "Net-(U12-OUT_A)") (class "Default")
      (node (ref "R96") (pin "2") (pinfunction "2_2") (pintype "passive"))
      (node (ref "U12") (pin "1") (pinfunction "OUT_A_1") (pintype "output"))
      (node (ref "U14") (pin "4") (pinfunction "Y7_4") (pintype "bidirectional"))
    )
    (net (code "53") (name "Net-(U12-OUT_B)") (class "Default")
      (node (ref "R97") (pin "2") (pinfunction "2_2") (pintype "passive"))
      (node (ref "U12") (pin "7") (pinfunction "OUT_B_7") (pintype "output"))
      (node (ref "U14") (pin "2") (pinfunction "Y6_2") (pintype "bidirectional"))
    )
    (net (code "54") (name "Net-(U13-Y0)") (class "Default")
      (node (ref "R83") (pin "2") (pinfunction "2_2") (pintype "passive"))
      (node (ref "U13") (pin "13") (pinfunction "Y0_13") (pintype "bidirectional"))
      (node (ref "U5") (pin "7") (pinfunction "OUT_B_7") (pintype "output"))
    )
    (net (code "55") (name "Net-(U13-Y1)") (class "Default")
      (node (ref "R82") (pin "2") (pinfunction "2_2") (pintype "passive"))
      (node (ref "U13") (pin "14") (pinfunction "Y1_14") (pintype "bidirectional"))
      (node (ref "U5") (pin "1") (pinfunction "OUT_A_1") (pintype "output"))
    )
    (net (code "56") (name "Net-(U13-Y2)") (class "Default")
      (node (ref "R85") (pin "2") (pinfunction "2_2") (pintype "passive"))
      (node (ref "U13") (pin "15") (pinfunction "Y2_15") (pintype "bidirectional"))
      (node (ref "U6") (pin "7") (pinfunction "OUT_B_7") (pintype "output"))
    )
    (net (code "57") (name "Net-(U13-Y3)") (class "Default")
      (node (ref "R84") (pin "2") (pinfunction "2_2") (pintype "passive"))
      (node (ref "U13") (pin "12") (pinfunction "Y3_12") (pintype "bidirectional"))
      (node (ref "U6") (pin "1") (pinfunction "OUT_A_1") (pintype "output"))
    )
    (net (code "58") (name "Net-(U13-Y4)") (class "Default")
      (node (ref "R87") (pin "2") (pinfunction "2_2") (pintype "passive"))
      (node (ref "U13") (pin "1") (pinfunction "Y4_1") (pintype "bidirectional"))
      (node (ref "U7") (pin "7") (pinfunction "OUT_B_7") (pintype "output"))
    )
    (net (code "59") (name "Net-(U13-Y5)") (class "Default")
      (node (ref "R24") (pin "2") (pinfunction "2_2") (pintype "passive"))
      (node (ref "U13") (pin "5") (pinfunction "Y5_5") (pintype "bidirectional"))
      (node (ref "U7") (pin "1") (pinfunction "OUT_A_1") (pintype "output"))
    )
    (net (code "60") (name "Net-(U13-Y6)") (class "Default")
      (node (ref "R89") (pin "2") (pinfunction "2_2") (pintype "passive"))
      (node (ref "U13") (pin "2") (pinfunction "Y6_2") (pintype "bidirectional"))
      (node (ref "U8") (pin "7") (pinfunction "OUT_B_7") (pintype "output"))
    )
    (net (code "61") (name "Net-(U13-Y7)") (class "Default")
      (node (ref "R88") (pin "2") (pinfunction "2_2") (pintype "passive"))
      (node (ref "U13") (pin "4") (pinfunction "Y7_4") (pintype "bidirectional"))
      (node (ref "U8") (pin "1") (pinfunction "OUT_A_1") (pintype "output"))
    )
    (net (code "62") (name "Net-(U14-Y0)") (class "Default")
      (node (ref "R91") (pin "2") (pinfunction "2_2") (pintype "passive"))
      (node (ref "U14") (pin "13") (pinfunction "Y0_13") (pintype "bidirectional"))
      (node (ref "U9") (pin "7") (pinfunction "OUT_B_7") (pintype "output"))
    )
    (net (code "63") (name "Net-(U14-Y1)") (class "Default")
      (node (ref "R32") (pin "2") (pinfunction "2_2") (pintype "passive"))
      (node (ref "U14") (pin "14") (pinfunction "Y1_14") (pintype "bidirectional"))
      (node (ref "U9") (pin "1") (pinfunction "OUT_A_1") (pintype "output"))
    )
    (net (code "64") (name "Net-(U15-+IN_A)") (class "Default")
      (node (ref "JP3") (pin "2") (pinfunction "2_2") (pintype "passive"))
      (node (ref "R49") (pin "1") (pinfunction "1_1") (pintype "passive"))
      (node (ref "U15") (pin "3") (pinfunction "+IN_A_3") (pintype "input"))
    )
    (net (code "65") (name "Net-(U15-+IN_B)") (class "Default")
      (node (ref "JP3") (pin "1") (pinfunction "1_1") (pintype "passive"))
      (node (ref "R50") (pin "1") (pinfunction "1_1") (pintype "passive"))
      (node (ref "U15") (pin "5") (pinfunction "+IN_B_5") (pintype "input"))
    )
    (net (code "66") (name "Net-(U15--IN_A)") (class "Default")
      (node (ref "R2") (pin "1") (pinfunction "1_1") (pintype "passive"))
      (node (ref "R3") (pin "2") (pinfunction "2_2") (pintype "passive"))
      (node (ref "U15") (pin "2") (pinfunction "-IN_A_2") (pintype "input"))
    )
    (net (code "67") (name "Net-(U15--IN_B)") (class "Default")
      (node (ref "R4") (pin "2") (pinfunction "2_2") (pintype "passive"))
      (node (ref "R5") (pin "1") (pinfunction "1_1") (pintype "passive"))
      (node (ref "U15") (pin "6") (pinfunction "-IN_B_6") (pintype "input"))
    )
    (net (code "68") (name "Net-(U15-OUT_A)") (class "Default")
      (node (ref "R2") (pin "2") (pinfunction "2_2") (pintype "passive"))
      (node (ref "U15") (pin "1") (pinfunction "OUT_A_1") (pintype "output"))
      (node (ref "U23") (pin "14") (pinfunction "Y1_14") (pintype "bidirectional"))
    )
    (net (code "69") (name "Net-(U15-OUT_B)") (class "Default")
      (node (ref "R5") (pin "2") (pinfunction "2_2") (pintype "passive"))
      (node (ref "U15") (pin "7") (pinfunction "OUT_B_7") (pintype "output"))
      (node (ref "U23") (pin "13") (pinfunction "Y0_13") (pintype "bidirectional"))
    )
    (net (code "70") (name "Net-(U16-+IN_A)") (class "Default")
      (node (ref "JP3") (pin "4") (pinfunction "4_4") (pintype "passive"))
      (node (ref "R53") (pin "1") (pinfunction "1_1") (pintype "passive"))
      (node (ref "U16") (pin "3") (pinfunction "+IN_A_3") (pintype "input"))
    )
    (net (code "71") (name "Net-(U16-+IN_B)") (class "Default")
      (node (ref "JP3") (pin "3") (pinfunction "3_3") (pintype "passive"))
      (node (ref "R54") (pin "1") (pinfunction "1_1") (pintype "passive"))
      (node (ref "U16") (pin "5") (pinfunction "+IN_B_5") (pintype "input"))
    )
    (net (code "72") (name "Net-(U16--IN_A)") (class "Default")
      (node (ref "R6") (pin "2") (pinfunction "2_2") (pintype "passive"))
      (node (ref "R7") (pin "1") (pinfunction "1_1") (pintype "passive"))
      (node (ref "U16") (pin "2") (pinfunction "-IN_A_2") (pintype "input"))
    )
    (net (code "73") (name "Net-(U16--IN_B)") (class "Default")
      (node (ref "R8") (pin "2") (pinfunction "2_2") (pintype "passive"))
      (node (ref "R9") (pin "1") (pinfunction "1_1") (pintype "passive"))
      (node (ref "U16") (pin "6") (pinfunction "-IN_B_6") (pintype "input"))
    )
    (net (code "74") (name "Net-(U16-OUT_A)") (class "Default")
      (node (ref "R7") (pin "2") (pinfunction "2_2") (pintype "passive"))
      (node (ref "U16") (pin "1") (pinfunction "OUT_A_1") (pintype "output"))
      (node (ref "U23") (pin "12") (pinfunction "Y3_12") (pintype "bidirectional"))
    )
    (net (code "75") (name "Net-(U16-OUT_B)") (class "Default")
      (node (ref "R9") (pin "2") (pinfunction "2_2") (pintype "passive"))
      (node (ref "U16") (pin "7") (pinfunction "OUT_B_7") (pintype "output"))
      (node (ref "U23") (pin "15") (pinfunction "Y2_15") (pintype "bidirectional"))
    )
    (net (code "76") (name "Net-(U17-+IN_A)") (class "Default")
      (node (ref "JP3") (pin "6") (pinfunction "6_6") (pintype "passive"))
      (node (ref "R57") (pin "1") (pinfunction "1_1") (pintype "passive"))
      (node (ref "U17") (pin "3") (pinfunction "+IN_A_3") (pintype "input"))
    )
    (net (code "77") (name "Net-(U17-+IN_B)") (class "Default")
      (node (ref "JP3") (pin "5") (pinfunction "5_5") (pintype "passive"))
      (node (ref "R58") (pin "1") (pinfunction "1_1") (pintype "passive"))
      (node (ref "U17") (pin "5") (pinfunction "+IN_B_5") (pintype "input"))
    )
    (net (code "78") (name "Net-(U17--IN_A)") (class "Default")
      (node (ref "R10") (pin "1") (pinfunction "1_1") (pintype "passive"))
      (node (ref "R11") (pin "2") (pinfunction "2_2") (pintype "passive"))
      (node (ref "U17") (pin "2") (pinfunction "-IN_A_2") (pintype "input"))
    )
    (net (code "79") (name "Net-(U17--IN_B)") (class "Default")
      (node (ref "R12") (pin "2") (pinfunction "2_2") (pintype "passive"))
      (node (ref "R13") (pin "1") (pinfunction "1_1") (pintype "passive"))
      (node (ref "U17") (pin "6") (pinfunction "-IN_B_6") (pintype "input"))
    )
    (net (code "80") (name "Net-(U17-OUT_A)") (class "Default")
      (node (ref "R10") (pin "2") (pinfunction "2_2") (pintype "passive"))
      (node (ref "U17") (pin "1") (pinfunction "OUT_A_1") (pintype "output"))
      (node (ref "U23") (pin "5") (pinfunction "Y5_5") (pintype "bidirectional"))
    )
    (net (code "81") (name "Net-(U17-OUT_B)") (class "Default")
      (node (ref "R13") (pin "2") (pinfunction "2_2") (pintype "passive"))
      (node (ref "U17") (pin "7") (pinfunction "OUT_B_7") (pintype "output"))
      (node (ref "U23") (pin "1") (pinfunction "Y4_1") (pintype "bidirectional"))
    )
    (net (code "82") (name "Net-(U18-+IN_A)") (class "Default")
      (node (ref "JP3") (pin "8") (pinfunction "8_8") (pintype "passive"))
      (node (ref "R61") (pin "1") (pinfunction "1_1") (pintype "passive"))
      (node (ref "U18") (pin "3") (pinfunction "+IN_A_3") (pintype "input"))
    )
    (net (code "83") (name "Net-(U18-+IN_B)") (class "Default")
      (node (ref "JP3") (pin "7") (pinfunction "7_7") (pintype "passive"))
      (node (ref "R62") (pin "1") (pinfunction "1_1") (pintype "passive"))
      (node (ref "U18") (pin "5") (pinfunction "+IN_B_5") (pintype "input"))
    )
    (net (code "84") (name "Net-(U18--IN_A)") (class "Default")
      (node (ref "R14") (pin "2") (pinfunction "2_2") (pintype "passive"))
      (node (ref "R15") (pin "1") (pinfunction "1_1") (pintype "passive"))
      (node (ref "U18") (pin "2") (pinfunction "-IN_A_2") (pintype "input"))
    )
    (net (code "85") (name "Net-(U18--IN_B)") (class "Default")
      (node (ref "R48") (pin "2") (pinfunction "2_2") (pintype "passive"))
      (node (ref "R51") (pin "1") (pinfunction "1_1") (pintype "passive"))
      (node (ref "U18") (pin "6") (pinfunction "-IN_B_6") (pintype "input"))
    )
    (net (code "86") (name "Net-(U18-OUT_A)") (class "Default")
      (node (ref "R15") (pin "2") (pinfunction "2_2") (pintype "passive"))
      (node (ref "U18") (pin "1") (pinfunction "OUT_A_1") (pintype "output"))
      (node (ref "U23") (pin "4") (pinfunction "Y7_4") (pintype "bidirectional"))
    )
    (net (code "87") (name "Net-(U18-OUT_B)") (class "Default")
      (node (ref "R51") (pin "2") (pinfunction "2_2") (pintype "passive"))
      (node (ref "U18") (pin "7") (pinfunction "OUT_B_7") (pintype "output"))
      (node (ref "U23") (pin "2") (pinfunction "Y6_2") (pintype "bidirectional"))
    )
    (net (code "88") (name "Net-(U19-+IN_A)") (class "Default")
      (node (ref "JP3") (pin "10") (pinfunction "10_10") (pintype "passive"))
      (node (ref "R65") (pin "1") (pinfunction "1_1") (pintype "passive"))
      (node (ref "U19") (pin "3") (pinfunction "+IN_A_3") (pintype "input"))
    )
    (net (code "89") (name "Net-(U19-+IN_B)") (class "Default")
      (node (ref "JP3") (pin "9") (pinfunction "9_9") (pintype "passive"))
      (node (ref "R66") (pin "1") (pinfunction "1_1") (pintype "passive"))
      (node (ref "U19") (pin "5") (pinfunction "+IN_B_5") (pintype "input"))
    )
    (net (code "90") (name "Net-(U19--IN_A)") (class "Default")
      (node (ref "R52") (pin "2") (pinfunction "2_2") (pintype "passive"))
      (node (ref "R55") (pin "1") (pinfunction "1_1") (pintype "passive"))
      (node (ref "U19") (pin "2") (pinfunction "-IN_A_2") (pintype "input"))
    )
    (net (code "91") (name "Net-(U19--IN_B)") (class "Default")
      (node (ref "R56") (pin "2") (pinfunction "2_2") (pintype "passive"))
      (node (ref "R59") (pin "1") (pinfunction "1_1") (pintype "passive"))
      (node (ref "U19") (pin "6") (pinfunction "-IN_B_6") (pintype "input"))
    )
    (net (code "92") (name "Net-(U19-OUT_A)") (class "Default")
      (node (ref "R55") (pin "2") (pinfunction "2_2") (pintype "passive"))
      (node (ref "U19") (pin "1") (pinfunction "OUT_A_1") (pintype "output"))
      (node (ref "U24") (pin "14") (pinfunction "Y1_14") (pintype "bidirectional"))
    )
    (net (code "93") (name "Net-(U19-OUT_B)") (class "Default")
      (node (ref "R59") (pin "2") (pinfunction "2_2") (pintype "passive"))
      (node (ref "U19") (pin "7") (pinfunction "OUT_B_7") (pintype "output"))
      (node (ref "U24") (pin "13") (pinfunction "Y0_13") (pintype "bidirectional"))
    )
    (net (code "94") (name "Net-(U20-+IN_A)") (class "Default")
      (node (ref "JP3") (pin "12") (pinfunction "12_12") (pintype "passive"))
      (node (ref "R69") (pin "1") (pinfunction "1_1") (pintype "passive"))
      (node (ref "U20") (pin "3") (pinfunction "+IN_A_3") (pintype "input"))
    )
    (net (code "95") (name "Net-(U20-+IN_B)") (class "Default")
      (node (ref "JP3") (pin "11") (pinfunction "11_11") (pintype "passive"))
      (node (ref "R70") (pin "1") (pinfunction "1_1") (pintype "passive"))
      (node (ref "U20") (pin "5") (pinfunction "+IN_B_5") (pintype "input"))
    )
    (net (code "96") (name "Net-(U20--IN_A)") (class "Default")
      (node (ref "R60") (pin "2") (pinfunction "2_2") (pintype "passive"))
      (node (ref "R63") (pin "1") (pinfunction "1_1") (pintype "passive"))
      (node (ref "U20") (pin "2") (pinfunction "-IN_A_2") (pintype "input"))
    )
    (net (code "97") (name "Net-(U20--IN_B)") (class "Default")
      (node (ref "R64") (pin "2") (pinfunction "2_2") (pintype "passive"))
      (node (ref "R67") (pin "1") (pinfunction "1_1") (pintype "passive"))
      (node (ref "U20") (pin "6") (pinfunction "-IN_B_6") (pintype "input"))
    )
    (net (code "98") (name "Net-(U20-OUT_A)") (class "Default")
      (node (ref "R63") (pin "2") (pinfunction "2_2") (pintype "passive"))
      (node (ref "U20") (pin "1") (pinfunction "OUT_A_1") (pintype "output"))
      (node (ref "U24") (pin "12") (pinfunction "Y3_12") (pintype "bidirectional"))
    )
    (net (code "99") (name "Net-(U20-OUT_B)") (class "Default")
      (node (ref "R67") (pin "2") (pinfunction "2_2") (pintype "passive"))
      (node (ref "U20") (pin "7") (pinfunction "OUT_B_7") (pintype "output"))
      (node (ref "U24") (pin "15") (pinfunction "Y2_15") (pintype "bidirectional"))
    )
    (net (code "100") (name "Net-(U21-+IN_A)") (class "Default")
      (node (ref "JP3") (pin "14") (pinfunction "14_14") (pintype "passive"))
      (node (ref "R73") (pin "1") (pinfunction "1_1") (pintype "passive"))
      (node (ref "U21") (pin "3") (pinfunction "+IN_A_3") (pintype "input"))
    )
    (net (code "101") (name "Net-(U21-+IN_B)") (class "Default")
      (node (ref "JP3") (pin "13") (pinfunction "13_13") (pintype "passive"))
      (node (ref "R74") (pin "1") (pinfunction "1_1") (pintype "passive"))
      (node (ref "U21") (pin "5") (pinfunction "+IN_B_5") (pintype "input"))
    )
    (net (code "102") (name "Net-(U21--IN_A)") (class "Default")
      (node (ref "R68") (pin "2") (pinfunction "2_2") (pintype "passive"))
      (node (ref "R71") (pin "1") (pinfunction "1_1") (pintype "passive"))
      (node (ref "U21") (pin "2") (pinfunction "-IN_A_2") (pintype "input"))
    )
    (net (code "103") (name "Net-(U21--IN_B)") (class "Default")
      (node (ref "R72") (pin "2") (pinfunction "2_2") (pintype "passive"))
      (node (ref "R75") (pin "1") (pinfunction "1_1") (pintype "passive"))
      (node (ref "U21") (pin "6") (pinfunction "-IN_B_6") (pintype "input"))
    )
    (net (code "104") (name "Net-(U21-OUT_A)") (class "Default")
      (node (ref "R71") (pin "2") (pinfunction "2_2") (pintype "passive"))
      (node (ref "U21") (pin "1") (pinfunction "OUT_A_1") (pintype "output"))
      (node (ref "U24") (pin "5") (pinfunction "Y5_5") (pintype "bidirectional"))
    )
    (net (code "105") (name "Net-(U21-OUT_B)") (class "Default")
      (node (ref "R75") (pin "2") (pinfunction "2_2") (pintype "passive"))
      (node (ref "U21") (pin "7") (pinfunction "OUT_B_7") (pintype "output"))
      (node (ref "U24") (pin "1") (pinfunction "Y4_1") (pintype "bidirectional"))
    )
    (net (code "106") (name "Net-(U22-+IN_A)") (class "Default")
      (node (ref "JP3") (pin "16") (pinfunction "16_16") (pintype "passive"))
      (node (ref "R77") (pin "1") (pinfunction "1_1") (pintype "passive"))
      (node (ref "U22") (pin "3") (pinfunction "+IN_A_3") (pintype "input"))
    )
    (net (code "107") (name "Net-(U22-+IN_B)") (class "Default")
      (node (ref "JP3") (pin "15") (pinfunction "15_15") (pintype "passive"))
      (node (ref "R78") (pin "1") (pinfunction "1_1") (pintype "passive"))
      (node (ref "U22") (pin "5") (pinfunction "+IN_B_5") (pintype "input"))
    )
    (net (code "108") (name "Net-(U22--IN_A)") (class "Default")
      (node (ref "R76") (pin "2") (pinfunction "2_2") (pintype "passive"))
      (node (ref "R80") (pin "1") (pinfunction "1_1") (pintype "passive"))
      (node (ref "U22") (pin "2") (pinfunction "-IN_A_2") (pintype "input"))
    )
    (net (code "109") (name "Net-(U22--IN_B)") (class "Default")
      (node (ref "R79") (pin "2") (pinfunction "2_2") (pintype "passive"))
      (node (ref "R81") (pin "1") (pinfunction "1_1") (pintype "passive"))
      (node (ref "U22") (pin "6") (pinfunction "-IN_B_6") (pintype "input"))
    )
    (net (code "110") (name "Net-(U22-OUT_A)") (class "Default")
      (node (ref "R80") (pin "2") (pinfunction "2_2") (pintype "passive"))
      (node (ref "U22") (pin "1") (pinfunction "OUT_A_1") (pintype "output"))
      (node (ref "U24") (pin "4") (pinfunction "Y7_4") (pintype "bidirectional"))
    )
    (net (code "111") (name "Net-(U22-OUT_B)") (class "Default")
      (node (ref "R81") (pin "2") (pinfunction "2_2") (pintype "passive"))
      (node (ref "U22") (pin "7") (pinfunction "OUT_B_7") (pintype "output"))
      (node (ref "U24") (pin "2") (pinfunction "Y6_2") (pintype "bidirectional"))
    )
    (net (code "112") (name "unconnected-(IC2-QH*-Pad9)") (class "Default")
      (node (ref "IC2") (pin "9") (pinfunction "QH*_9") (pintype "tri_state"))
    )
    (net (code "113") (name "unconnected-(IC2-QH-Pad7)") (class "Default")
      (node (ref "IC2") (pin "7") (pinfunction "QH_7") (pintype "tri_state"))
    )
    (net (code "114") (name "unconnected-(MOTHERBOARD-Pad7)") (class "Default")
      (node (ref "MOTHERBOARD") (pin "7") (pinfunction "7_7") (pintype "passive"))
    )
  )
)
